# TD3_Filter_dsPIC33EP128GP502.net
KiCad netlist of a schematic drawn in EAGLE
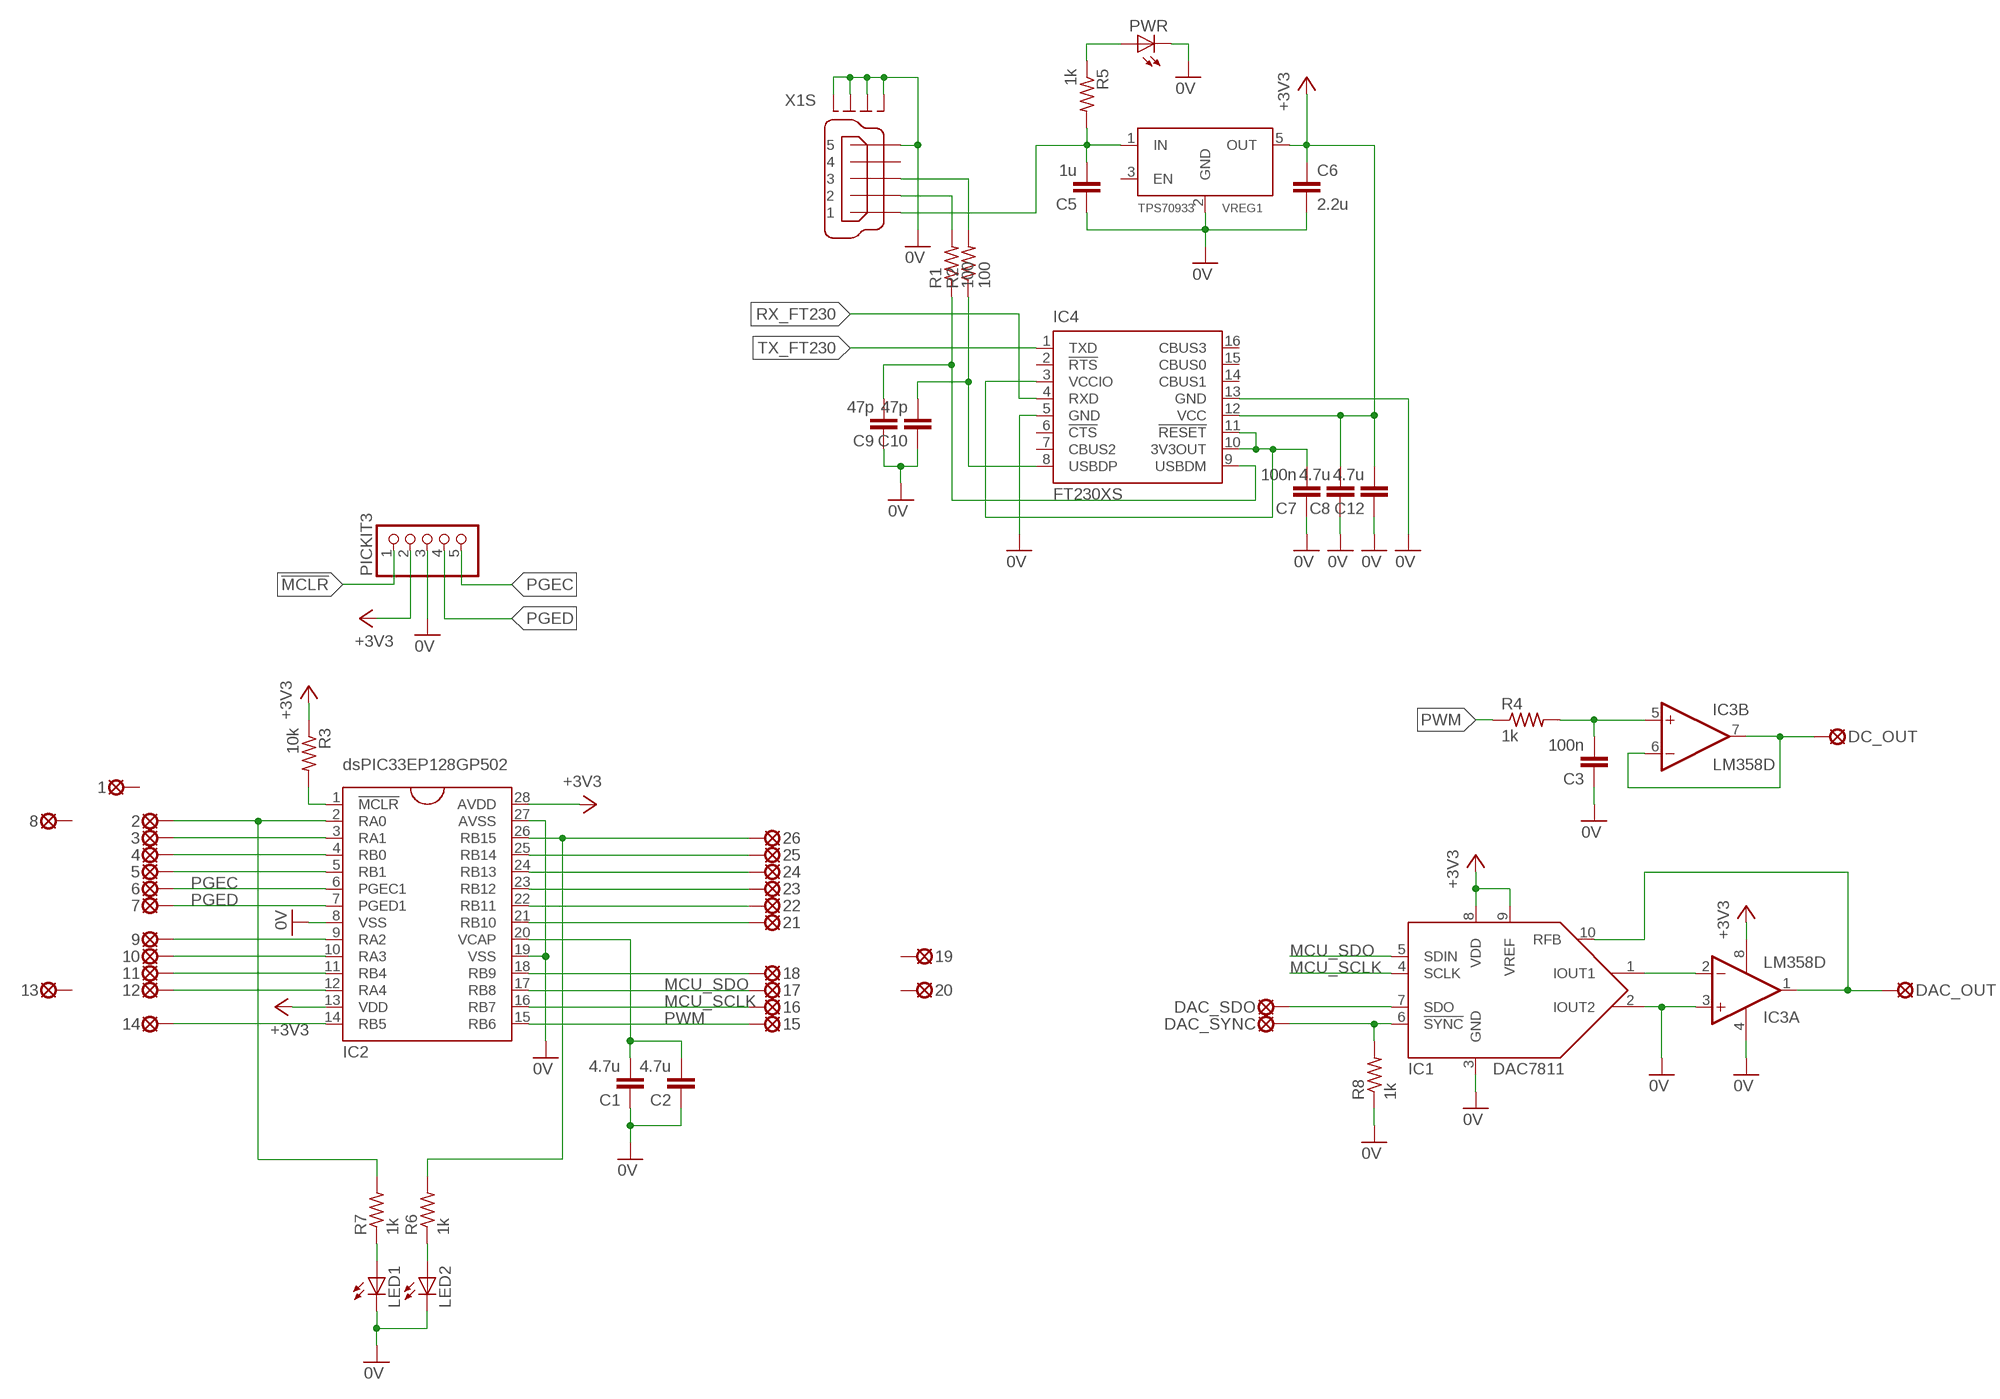
[diagram p0: schematic, sheet 1]

(export (version "E")
  (design (tool "Eeschema 10.0.6"))
  (components
    (comp (ref "1")
      (value "LSP10")
      (footprint "eagle-import:LSP10")
      (libsource (lib "eagle-import") (part "LSP10"))
    )
    (comp (ref "2")
      (value "LSP10")
      (footprint "eagle-import:LSP10")
      (libsource (lib "eagle-import") (part "LSP10"))
    )
    (comp (ref "3")
      (value "LSP10")
      (footprint "eagle-import:LSP10")
      (libsource (lib "eagle-import") (part "LSP10"))
    )
    (comp (ref "4")
      (value "LSP10")
      (footprint "eagle-import:LSP10")
      (libsource (lib "eagle-import") (part "LSP10"))
    )
    (comp (ref "5")
      (value "LSP10")
      (footprint "eagle-import:LSP10")
      (libsource (lib "eagle-import") (part "LSP10"))
    )
    (comp (ref "6")
      (value "LSP10")
      (footprint "eagle-import:LSP10")
      (libsource (lib "eagle-import") (part "LSP10"))
    )
    (comp (ref "7")
      (value "LSP10")
      (footprint "eagle-import:LSP10")
      (libsource (lib "eagle-import") (part "LSP10"))
    )
    (comp (ref "8")
      (value "LSP10")
      (footprint "eagle-import:LSP10")
      (libsource (lib "eagle-import") (part "LSP10"))
    )
    (comp (ref "9")
      (value "LSP10")
      (footprint "eagle-import:LSP10")
      (libsource (lib "eagle-import") (part "LSP10"))
    )
    (comp (ref "10")
      (value "LSP10")
      (footprint "eagle-import:LSP10")
      (libsource (lib "eagle-import") (part "LSP10"))
    )
    (comp (ref "11")
      (value "LSP10")
      (footprint "eagle-import:LSP10")
      (libsource (lib "eagle-import") (part "LSP10"))
    )
    (comp (ref "12")
      (value "LSP10")
      (footprint "eagle-import:LSP10")
      (libsource (lib "eagle-import") (part "LSP10"))
    )
    (comp (ref "13")
      (value "LSP10")
      (footprint "eagle-import:LSP10")
      (libsource (lib "eagle-import") (part "LSP10"))
    )
    (comp (ref "14")
      (value "LSP10")
      (footprint "eagle-import:LSP10")
      (libsource (lib "eagle-import") (part "LSP10"))
    )
    (comp (ref "15")
      (value "LSP10")
      (footprint "eagle-import:LSP10")
      (libsource (lib "eagle-import") (part "LSP10"))
    )
    (comp (ref "16")
      (value "LSP10")
      (footprint "eagle-import:LSP10")
      (libsource (lib "eagle-import") (part "LSP10"))
    )
    (comp (ref "17")
      (value "LSP10")
      (footprint "eagle-import:LSP10")
      (libsource (lib "eagle-import") (part "LSP10"))
    )
    (comp (ref "18")
      (value "LSP10")
      (footprint "eagle-import:LSP10")
      (libsource (lib "eagle-import") (part "LSP10"))
    )
    (comp (ref "19")
      (value "LSP10")
      (footprint "eagle-import:LSP10")
      (libsource (lib "eagle-import") (part "LSP10"))
    )
    (comp (ref "20")
      (value "LSP10")
      (footprint "eagle-import:LSP10")
      (libsource (lib "eagle-import") (part "LSP10"))
    )
    (comp (ref "21")
      (value "LSP10")
      (footprint "eagle-import:LSP10")
      (libsource (lib "eagle-import") (part "LSP10"))
    )
    (comp (ref "22")
      (value "LSP10")
      (footprint "eagle-import:LSP10")
      (libsource (lib "eagle-import") (part "LSP10"))
    )
    (comp (ref "23")
      (value "LSP10")
      (footprint "eagle-import:LSP10")
      (libsource (lib "eagle-import") (part "LSP10"))
    )
    (comp (ref "24")
      (value "LSP10")
      (footprint "eagle-import:LSP10")
      (libsource (lib "eagle-import") (part "LSP10"))
    )
    (comp (ref "25")
      (value "LSP10")
      (footprint "eagle-import:LSP10")
      (libsource (lib "eagle-import") (part "LSP10"))
    )
    (comp (ref "26")
      (value "LSP10")
      (footprint "eagle-import:LSP10")
      (libsource (lib "eagle-import") (part "LSP10"))
    )
    (comp (ref "C1")
      (value "4.7u")
      (footprint "eagle-import:C1206")
      (libsource (lib "eagle-import") (part "C-EUC1206"))
    )
    (comp (ref "C2")
      (value "4.7u")
      (footprint "eagle-import:C1206")
      (libsource (lib "eagle-import") (part "C-EUC1206"))
    )
    (comp (ref "C3")
      (value "100n")
      (footprint "eagle-import:C1206")
      (libsource (lib "eagle-import") (part "C-EUC1206"))
    )
    (comp (ref "C5")
      (value "1u")
      (footprint "eagle-import:C1206")
      (libsource (lib "eagle-import") (part "C-EUC1206"))
    )
    (comp (ref "C6")
      (value "2.2u")
      (footprint "eagle-import:C1206")
      (libsource (lib "eagle-import") (part "C-EUC1206"))
    )
    (comp (ref "C7")
      (value "100n")
      (footprint "eagle-import:C1206")
      (libsource (lib "eagle-import") (part "C-EUC1206"))
    )
    (comp (ref "C8")
      (value "4.7u")
      (footprint "eagle-import:C1206")
      (libsource (lib "eagle-import") (part "C-EUC1206"))
    )
    (comp (ref "C9")
      (value "47p")
      (footprint "eagle-import:C1206")
      (libsource (lib "eagle-import") (part "C-EUC1206"))
    )
    (comp (ref "C10")
      (value "47p")
      (footprint "eagle-import:C1206")
      (libsource (lib "eagle-import") (part "C-EUC1206"))
    )
    (comp (ref "C12")
      (value "4.7u")
      (footprint "eagle-import:C1206")
      (libsource (lib "eagle-import") (part "C-EUC1206"))
    )
    (comp (ref "DAC_OUT")
      (value "LSP10")
      (footprint "eagle-import:LSP10")
      (libsource (lib "eagle-import") (part "LSP10"))
    )
    (comp (ref "DAC_SDO")
      (value "LSP10")
      (footprint "eagle-import:LSP10")
      (libsource (lib "eagle-import") (part "LSP10"))
    )
    (comp (ref "DAC_SYNC")
      (value "LSP10")
      (footprint "eagle-import:LSP10")
      (libsource (lib "eagle-import") (part "LSP10"))
    )
    (comp (ref "DC_OUT")
      (value "LSP10")
      (footprint "eagle-import:LSP10")
      (libsource (lib "eagle-import") (part "LSP10"))
    )
    (comp (ref "IC1")
      (value "DAC7811")
      (footprint "eagle-import:S-PDSO-G10")
      (libsource (lib "eagle-import") (part "DAC7811"))
    )
    (comp (ref "IC2")
      (value "DSPIC33EP128GP502")
      (footprint "eagle-import:DIL28")
      (libsource (lib "eagle-import") (part "DSPIC33EP128GP502"))
    )
    (comp (ref "IC3")
      (value "LM358D")
      (footprint "eagle-import:SO08")
      (libsource (lib "eagle-import") (part "LM358D"))
    )
    (comp (ref "IC4")
      (value "FT230XS")
      (footprint "eagle-import:SSOP16")
      (libsource (lib "eagle-import") (part "FT230XS"))
    )
    (comp (ref "LED1")
      (value "LED3MM")
      (footprint "eagle-import:LED3MM")
      (libsource (lib "eagle-import") (part "LED3MM"))
    )
    (comp (ref "LED2")
      (value "LED3MM")
      (footprint "eagle-import:LED3MM")
      (libsource (lib "eagle-import") (part "LED3MM"))
    )
    (comp (ref "PICKIT3")
      (value "PINHD-1X5")
      (footprint "eagle-import:1X05")
      (libsource (lib "eagle-import") (part "PINHD-1X5"))
    )
    (comp (ref "PWR")
      (value "LED3MM")
      (footprint "eagle-import:LED3MM")
      (libsource (lib "eagle-import") (part "LED3MM"))
    )
    (comp (ref "R1")
      (value "100")
      (footprint "eagle-import:R0805")
      (libsource (lib "eagle-import") (part "R-US_R0805"))
    )
    (comp (ref "R2")
      (value "100")
      (footprint "eagle-import:R1206")
      (libsource (lib "eagle-import") (part "R-US_R1206"))
    )
    (comp (ref "R3")
      (value "10k")
      (footprint "eagle-import:R0805")
      (libsource (lib "eagle-import") (part "R-US_R0805"))
    )
    (comp (ref "R4")
      (value "1k")
      (footprint "eagle-import:R0805")
      (libsource (lib "eagle-import") (part "R-US_R0805"))
    )
    (comp (ref "R5")
      (value "1k")
      (footprint "eagle-import:R0805")
      (libsource (lib "eagle-import") (part "R-US_R0805"))
    )
    (comp (ref "R6")
      (value "1k")
      (footprint "eagle-import:R0805")
      (libsource (lib "eagle-import") (part "R-US_R0805"))
    )
    (comp (ref "R7")
      (value "1k")
      (footprint "eagle-import:R0805")
      (libsource (lib "eagle-import") (part "R-US_R0805"))
    )
    (comp (ref "R8")
      (value "1k")
      (footprint "eagle-import:R0805")
      (libsource (lib "eagle-import") (part "R-US_R0805"))
    )
    (comp (ref "VREG1")
      (value "TPS70933")
      (footprint "eagle-import:TPS70933")
      (libsource (lib "eagle-import") (part "TPS70933"))
    )
    (comp (ref "X1")
      (value "MINI-USB_SHIELD5P4-32005-400")
      (footprint "eagle-import:32005-400")
      (libsource (lib "eagle-import") (part "MINI-USB_SHIELD5P4-32005-400"))
    )
  )
  (nets
    (net (code "1") (name "+3V3") (class "Default")
      (node (ref "C12") (pin "2") (pinfunction "2_2") (pintype "passive"))
      (node (ref "C6") (pin "1") (pinfunction "1_1") (pintype "passive"))
      (node (ref "C8") (pin "2") (pinfunction "2_2") (pintype "passive"))
      (node (ref "IC1") (pin "8") (pinfunction "VDD_8") (pintype "bidirectional"))
      (node (ref "IC1") (pin "9") (pinfunction "VREF_9") (pintype "bidirectional"))
      (node (ref "IC2") (pin "13") (pinfunction "VDD_13") (pintype "bidirectional"))
      (node (ref "IC2") (pin "28") (pinfunction "AVDD_28") (pintype "bidirectional"))
      (node (ref "IC3") (pin "8") (pinfunction "V+_8") (pintype "power_in"))
      (node (ref "IC4") (pin "12") (pinfunction "VCC_12") (pintype "power_in"))
      (node (ref "PICKIT3") (pin "2") (pinfunction "2_2") (pintype "passive"))
      (node (ref "R3") (pin "1") (pinfunction "1_1") (pintype "passive"))
      (node (ref "VREG1") (pin "5") (pinfunction "OUT_5") (pintype "bidirectional"))
    )
    (net (code "2") (name "/MCU_SCLK") (class "Default")
      (node (ref "16") (pin "MP") (pinfunction "MP_MP") (pintype "passive"))
      (node (ref "IC1") (pin "4") (pinfunction "SCLK_4") (pintype "bidirectional"))
      (node (ref "IC2") (pin "16") (pinfunction "RB7_16") (pintype "bidirectional"))
    )
    (net (code "3") (name "/MCU_SDO") (class "Default")
      (node (ref "17") (pin "MP") (pinfunction "MP_MP") (pintype "passive"))
      (node (ref "IC1") (pin "5") (pinfunction "SDIN_5") (pintype "bidirectional"))
      (node (ref "IC2") (pin "17") (pinfunction "RB8_17") (pintype "bidirectional"))
    )
    (net (code "4") (name "/~{MCLR}") (class "Default")
      (node (ref "PICKIT3") (pin "1") (pinfunction "1_1") (pintype "passive"))
    )
    (net (code "5") (name "0V") (class "Default")
      (node (ref "C1") (pin "1") (pinfunction "1_1") (pintype "passive"))
      (node (ref "C10") (pin "1") (pinfunction "1_1") (pintype "passive"))
      (node (ref "C12") (pin "1") (pinfunction "1_1") (pintype "passive"))
      (node (ref "C2") (pin "1") (pinfunction "1_1") (pintype "passive"))
      (node (ref "C3") (pin "1") (pinfunction "1_1") (pintype "passive"))
      (node (ref "C5") (pin "1") (pinfunction "1_1") (pintype "passive"))
      (node (ref "C6") (pin "2") (pinfunction "2_2") (pintype "passive"))
      (node (ref "C7") (pin "1") (pinfunction "1_1") (pintype "passive"))
      (node (ref "C8") (pin "1") (pinfunction "1_1") (pintype "passive"))
      (node (ref "C9") (pin "1") (pinfunction "1_1") (pintype "passive"))
      (node (ref "IC1") (pin "2") (pinfunction "IOUT2_2") (pintype "bidirectional"))
      (node (ref "IC1") (pin "3") (pinfunction "GND_3") (pintype "bidirectional"))
      (node (ref "IC2") (pin "19") (pinfunction "VSS_19") (pintype "bidirectional"))
      (node (ref "IC2") (pin "27") (pinfunction "AVSS_27") (pintype "bidirectional"))
      (node (ref "IC2") (pin "8") (pinfunction "VSS_8") (pintype "bidirectional"))
      (node (ref "IC3") (pin "3") (pinfunction "+IN_3") (pintype "input"))
      (node (ref "IC3") (pin "4") (pinfunction "V-_4") (pintype "power_in"))
      (node (ref "IC4") (pin "13") (pinfunction "GND_13") (pintype "power_in"))
      (node (ref "IC4") (pin "5") (pinfunction "GND_5") (pintype "power_in"))
      (node (ref "LED1") (pin "K") (pinfunction "C_K") (pintype "passive"))
      (node (ref "LED2") (pin "K") (pinfunction "C_K") (pintype "passive"))
      (node (ref "PICKIT3") (pin "3") (pinfunction "3_3") (pintype "passive"))
      (node (ref "PWR") (pin "K") (pinfunction "C_K") (pintype "passive"))
      (node (ref "R8") (pin "1") (pinfunction "1_1") (pintype "passive"))
      (node (ref "VREG1") (pin "2") (pinfunction "GND_2") (pintype "bidirectional"))
      (node (ref "X1") (pin "5") (pinfunction "5_5") (pintype "passive"))
      (node (ref "X1") (pin "M1") (pinfunction "S1_M1") (pintype "passive"))
      (node (ref "X1") (pin "M2") (pinfunction "S2_M2") (pintype "passive"))
      (node (ref "X1") (pin "M3") (pinfunction "S3_M3") (pintype "passive"))
      (node (ref "X1") (pin "M4") (pinfunction "S4_M4") (pintype "passive"))
    )
    (net (code "6") (name "Net-(IC1-IOUT1)") (class "Default")
      (node (ref "IC1") (pin "1") (pinfunction "IOUT1_1") (pintype "bidirectional"))
      (node (ref "IC3") (pin "2") (pinfunction "-IN_2") (pintype "input"))
    )
    (net (code "7") (name "Net-(IC1-RFB)") (class "Default")
      (node (ref "DAC_OUT") (pin "MP") (pinfunction "MP_MP") (pintype "passive"))
      (node (ref "IC1") (pin "10") (pinfunction "RFB_10") (pintype "bidirectional"))
      (node (ref "IC3") (pin "1") (pinfunction "OUT_1") (pintype "output"))
    )
    (net (code "8") (name "Net-(IC1-SDO)") (class "Default")
      (node (ref "DAC_SDO") (pin "MP") (pinfunction "MP_MP") (pintype "passive"))
      (node (ref "IC1") (pin "7") (pinfunction "SDO_7") (pintype "bidirectional"))
    )
    (net (code "9") (name "Net-(IC1-~{SYNC})") (class "Default")
      (node (ref "DAC_SYNC") (pin "MP") (pinfunction "MP_MP") (pintype "passive"))
      (node (ref "IC1") (pin "6") (pinfunction "~{SYNC}_6") (pintype "bidirectional"))
      (node (ref "R8") (pin "2") (pinfunction "2_2") (pintype "passive"))
    )
    (net (code "10") (name "Net-(IC2-RA0)") (class "Default")
      (node (ref "2") (pin "MP") (pinfunction "MP_MP") (pintype "passive"))
      (node (ref "IC2") (pin "2") (pinfunction "RA0_2") (pintype "bidirectional"))
      (node (ref "R7") (pin "2") (pinfunction "2_2") (pintype "passive"))
    )
    (net (code "11") (name "Net-(IC2-RA1)") (class "Default")
      (node (ref "3") (pin "MP") (pinfunction "MP_MP") (pintype "passive"))
      (node (ref "IC2") (pin "3") (pinfunction "RA1_3") (pintype "bidirectional"))
    )
    (net (code "12") (name "Net-(IC2-RA2)") (class "Default")
      (node (ref "9") (pin "MP") (pinfunction "MP_MP") (pintype "passive"))
      (node (ref "IC2") (pin "9") (pinfunction "RA2_9") (pintype "bidirectional"))
    )
    (net (code "13") (name "Net-(IC2-RA3)") (class "Default")
      (node (ref "10") (pin "MP") (pinfunction "MP_MP") (pintype "passive"))
      (node (ref "IC2") (pin "10") (pinfunction "RA3_10") (pintype "bidirectional"))
    )
    (net (code "14") (name "Net-(IC2-RA4)") (class "Default")
      (node (ref "12") (pin "MP") (pinfunction "MP_MP") (pintype "passive"))
      (node (ref "IC2") (pin "12") (pinfunction "RA4_12") (pintype "bidirectional"))
    )
    (net (code "15") (name "Net-(IC2-RB0)") (class "Default")
      (node (ref "4") (pin "MP") (pinfunction "MP_MP") (pintype "passive"))
      (node (ref "IC2") (pin "4") (pinfunction "RB0_4") (pintype "bidirectional"))
    )
    (net (code "16") (name "Net-(IC2-RB1)") (class "Default")
      (node (ref "5") (pin "MP") (pinfunction "MP_MP") (pintype "passive"))
      (node (ref "IC2") (pin "5") (pinfunction "RB1_5") (pintype "bidirectional"))
    )
    (net (code "17") (name "Net-(IC2-RB4)") (class "Default")
      (node (ref "11") (pin "MP") (pinfunction "MP_MP") (pintype "passive"))
      (node (ref "IC2") (pin "11") (pinfunction "RB4_11") (pintype "bidirectional"))
    )
    (net (code "18") (name "Net-(IC2-RB5)") (class "Default")
      (node (ref "14") (pin "MP") (pinfunction "MP_MP") (pintype "passive"))
      (node (ref "IC2") (pin "14") (pinfunction "RB5_14") (pintype "bidirectional"))
    )
    (net (code "19") (name "Net-(IC2-RB9)") (class "Default")
      (node (ref "18") (pin "MP") (pinfunction "MP_MP") (pintype "passive"))
      (node (ref "IC2") (pin "18") (pinfunction "RB9_18") (pintype "bidirectional"))
    )
    (net (code "20") (name "Net-(IC2-RB10)") (class "Default")
      (node (ref "21") (pin "MP") (pinfunction "MP_MP") (pintype "passive"))
      (node (ref "IC2") (pin "21") (pinfunction "RB10_21") (pintype "bidirectional"))
    )
    (net (code "21") (name "Net-(IC2-RB11)") (class "Default")
      (node (ref "22") (pin "MP") (pinfunction "MP_MP") (pintype "passive"))
      (node (ref "IC2") (pin "22") (pinfunction "RB11_22") (pintype "bidirectional"))
    )
    (net (code "22") (name "Net-(IC2-RB12)") (class "Default")
      (node (ref "23") (pin "MP") (pinfunction "MP_MP") (pintype "passive"))
      (node (ref "IC2") (pin "23") (pinfunction "RB12_23") (pintype "bidirectional"))
    )
    (net (code "23") (name "Net-(IC2-RB13)") (class "Default")
      (node (ref "24") (pin "MP") (pinfunction "MP_MP") (pintype "passive"))
      (node (ref "IC2") (pin "24") (pinfunction "RB13_24") (pintype "bidirectional"))
    )
    (net (code "24") (name "Net-(IC2-RB14)") (class "Default")
      (node (ref "25") (pin "MP") (pinfunction "MP_MP") (pintype "passive"))
      (node (ref "IC2") (pin "25") (pinfunction "RB14_25") (pintype "bidirectional"))
    )
    (net (code "25") (name "Net-(IC2-RB15)") (class "Default")
      (node (ref "26") (pin "MP") (pinfunction "MP_MP") (pintype "passive"))
      (node (ref "IC2") (pin "26") (pinfunction "RB15_26") (pintype "bidirectional"))
      (node (ref "R6") (pin "2") (pinfunction "2_2") (pintype "passive"))
    )
    (net (code "26") (name "Net-(IC2-VCAP)") (class "Default")
      (node (ref "C1") (pin "2") (pinfunction "2_2") (pintype "passive"))
      (node (ref "C2") (pin "2") (pinfunction "2_2") (pintype "passive"))
      (node (ref "IC2") (pin "20") (pinfunction "VCAP_20") (pintype "bidirectional"))
    )
    (net (code "27") (name "Net-(IC2-~{MCLR})") (class "Default")
      (node (ref "IC2") (pin "1") (pinfunction "~{MCLR}_1") (pintype "bidirectional"))
      (node (ref "R3") (pin "2") (pinfunction "2_2") (pintype "passive"))
    )
    (net (code "28") (name "Net-(IC3B-+IN)") (class "Default")
      (node (ref "C3") (pin "2") (pinfunction "2_2") (pintype "passive"))
      (node (ref "IC3") (pin "5") (pinfunction "+IN_5") (pintype "input"))
      (node (ref "R4") (pin "2") (pinfunction "2_2") (pintype "passive"))
    )
    (net (code "29") (name "Net-(IC3B--IN)") (class "Default")
      (node (ref "DC_OUT") (pin "MP") (pinfunction "MP_MP") (pintype "passive"))
      (node (ref "IC3") (pin "6") (pinfunction "-IN_6") (pintype "input"))
      (node (ref "IC3") (pin "7") (pinfunction "OUT_7") (pintype "output"))
    )
    (net (code "30") (name "Net-(IC4-3V3OUT)") (class "Default")
      (node (ref "C7") (pin "2") (pinfunction "2_2") (pintype "passive"))
      (node (ref "IC4") (pin "10") (pinfunction "3V3OUT_10") (pintype "output"))
      (node (ref "IC4") (pin "11") (pinfunction "~{RESET}_11") (pintype "input"))
      (node (ref "IC4") (pin "3") (pinfunction "VCCIO_3") (pintype "power_in"))
    )
    (net (code "31") (name "Net-(IC4-USBDM)") (class "Default")
      (node (ref "C9") (pin "2") (pinfunction "2_2") (pintype "passive"))
      (node (ref "IC4") (pin "9") (pinfunction "USBDM_9") (pintype "input"))
      (node (ref "R1") (pin "1") (pinfunction "1_1") (pintype "passive"))
    )
    (net (code "32") (name "Net-(IC4-USBDP)") (class "Default")
      (node (ref "C10") (pin "2") (pinfunction "2_2") (pintype "passive"))
      (node (ref "IC4") (pin "8") (pinfunction "USBDP_8") (pintype "input"))
      (node (ref "R2") (pin "1") (pinfunction "1_1") (pintype "passive"))
    )
    (net (code "33") (name "Net-(LED1-PadA)") (class "Default")
      (node (ref "LED1") (pin "A") (pinfunction "A_A") (pintype "passive"))
      (node (ref "R7") (pin "1") (pinfunction "1_1") (pintype "passive"))
    )
    (net (code "34") (name "Net-(LED2-PadA)") (class "Default")
      (node (ref "LED2") (pin "A") (pinfunction "A_A") (pintype "passive"))
      (node (ref "R6") (pin "1") (pinfunction "1_1") (pintype "passive"))
    )
    (net (code "35") (name "Net-(PWR-PadA)") (class "Default")
      (node (ref "PWR") (pin "A") (pinfunction "A_A") (pintype "passive"))
      (node (ref "R5") (pin "1") (pinfunction "1_1") (pintype "passive"))
    )
    (net (code "36") (name "Net-(R1-Pad2)") (class "Default")
      (node (ref "R1") (pin "2") (pinfunction "2_2") (pintype "passive"))
      (node (ref "X1") (pin "2") (pinfunction "2_2") (pintype "passive"))
    )
    (net (code "37") (name "Net-(R2-Pad2)") (class "Default")
      (node (ref "R2") (pin "2") (pinfunction "2_2") (pintype "passive"))
      (node (ref "X1") (pin "3") (pinfunction "3_3") (pintype "passive"))
    )
    (net (code "38") (name "Net-(VREG1-IN)") (class "Default")
      (node (ref "C5") (pin "2") (pinfunction "2_2") (pintype "passive"))
      (node (ref "R5") (pin "2") (pinfunction "2_2") (pintype "passive"))
      (node (ref "VREG1") (pin "1") (pinfunction "IN_1") (pintype "bidirectional"))
      (node (ref "X1") (pin "1") (pinfunction "1_1") (pintype "passive"))
    )
    (net (code "39") (name "PGEC") (class "Default")
      (node (ref "6") (pin "MP") (pinfunction "MP_MP") (pintype "passive"))
      (node (ref "IC2") (pin "6") (pinfunction "PGEC1_6") (pintype "bidirectional"))
      (node (ref "PICKIT3") (pin "5") (pinfunction "5_5") (pintype "passive"))
    )
    (net (code "40") (name "PGED") (class "Default")
      (node (ref "7") (pin "MP") (pinfunction "MP_MP") (pintype "passive"))
      (node (ref "IC2") (pin "7") (pinfunction "PGED1_7") (pintype "bidirectional"))
      (node (ref "PICKIT3") (pin "4") (pinfunction "4_4") (pintype "passive"))
    )
    (net (code "41") (name "PWM") (class "Default")
      (node (ref "15") (pin "MP") (pinfunction "MP_MP") (pintype "passive"))
      (node (ref "IC2") (pin "15") (pinfunction "RB6_15") (pintype "bidirectional"))
      (node (ref "R4") (pin "1") (pinfunction "1_1") (pintype "passive"))
    )
    (net (code "42") (name "RX_FT230") (class "Default")
      (node (ref "IC4") (pin "4") (pinfunction "RXD_4") (pintype "input"))
    )
    (net (code "43") (name "TX_FT230") (class "Default")
      (node (ref "IC4") (pin "1") (pinfunction "TXD_1") (pintype "output"))
    )
    (net (code "44") (name "unconnected-(1-PadMP)") (class "Default")
      (node (ref "1") (pin "MP") (pinfunction "MP_MP") (pintype "passive"))
    )
    (net (code "45") (name "unconnected-(8-PadMP)") (class "Default")
      (node (ref "8") (pin "MP") (pinfunction "MP_MP") (pintype "passive"))
    )
    (net (code "46") (name "unconnected-(13-PadMP)") (class "Default")
      (node (ref "13") (pin "MP") (pinfunction "MP_MP") (pintype "passive"))
    )
    (net (code "47") (name "unconnected-(19-PadMP)") (class "Default")
      (node (ref "19") (pin "MP") (pinfunction "MP_MP") (pintype "passive"))
    )
    (net (code "48") (name "unconnected-(20-PadMP)") (class "Default")
      (node (ref "20") (pin "MP") (pinfunction "MP_MP") (pintype "passive"))
    )
    (net (code "49") (name "unconnected-(IC4-CBUS0-Pad15)") (class "Default")
      (node (ref "IC4") (pin "15") (pinfunction "CBUS0_15") (pintype "bidirectional"))
    )
    (net (code "50") (name "unconnected-(IC4-CBUS1-Pad14)") (class "Default")
      (node (ref "IC4") (pin "14") (pinfunction "CBUS1_14") (pintype "bidirectional"))
    )
    (net (code "51") (name "unconnected-(IC4-CBUS2-Pad7)") (class "Default")
      (node (ref "IC4") (pin "7") (pinfunction "CBUS2_7") (pintype "bidirectional"))
    )
    (net (code "52") (name "unconnected-(IC4-CBUS3-Pad16)") (class "Default")
      (node (ref "IC4") (pin "16") (pinfunction "CBUS3_16") (pintype "bidirectional"))
    )
    (net (code "53") (name "unconnected-(IC4-~{CTS}-Pad6)") (class "Default")
      (node (ref "IC4") (pin "6") (pinfunction "~{CTS}_6") (pintype "input"))
    )
    (net (code "54") (name "unconnected-(IC4-~{RTS}-Pad2)") (class "Default")
      (node (ref "IC4") (pin "2") (pinfunction "~{RTS}_2") (pintype "output"))
    )
    (net (code "55") (name "unconnected-(VREG1-EN-Pad3)") (class "Default")
      (node (ref "VREG1") (pin "3") (pinfunction "EN_3") (pintype "bidirectional"))
    )
    (net (code "56") (name "unconnected-(X1-Pad4)") (class "Default")
      (node (ref "X1") (pin "4") (pinfunction "4_4") (pintype "passive"))
    )
  )
)
